# MCU.net
KiCad netlist of a schematic drawn in Altium Designer
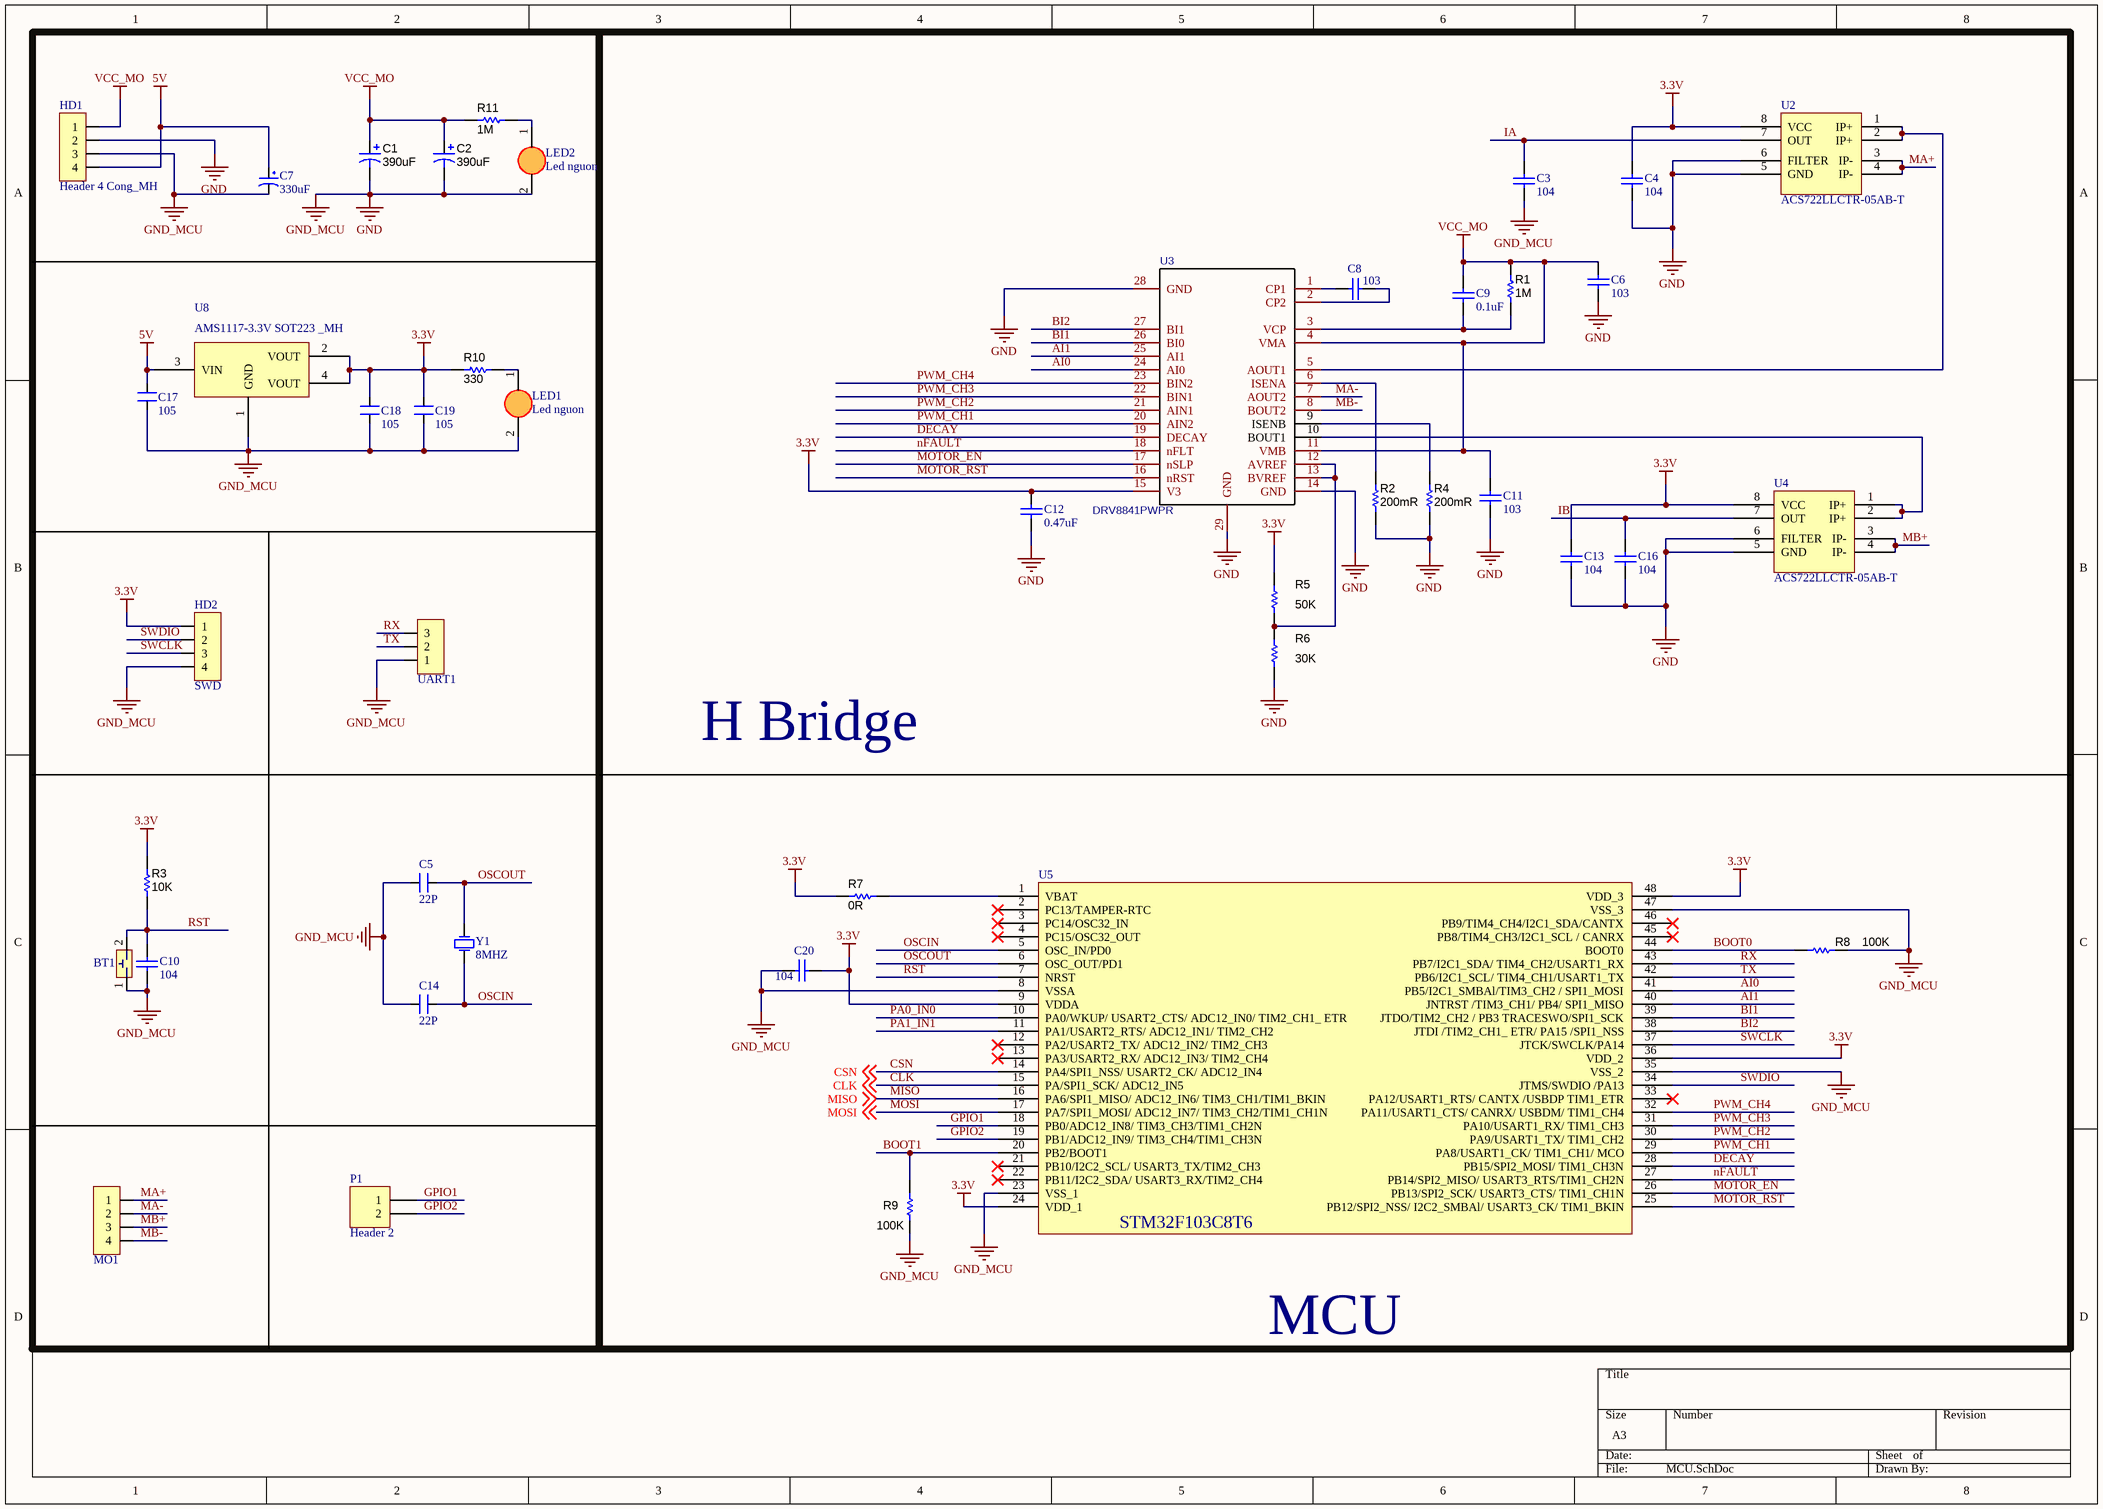
[diagram p0: MCU.SchDoc]

(export (version "E")
  (design (tool "Eeschema 10.0.6"))
  (components
    (comp (ref "BT1")
      (value "BUTTON 4P SMD_MH")
      (footprint "BUTTON 2P SMD")
      (description "Nút nhấn 4 chân, dán")
      (libsource (lib "MH_DA_THU_VIEN_16122016") (part "BUTTON 4P SMD_MH"))
    )
    (comp (ref "C1")
      (value "390uF")
      (footprint "CP1/3.0")
      (fields
        (field (name "PARTNUMBER") "UHW1H391MPD6")
        (field (name "MANUFACTURER") "Nichicon")
        (field (name "VALUEDISPLAYED") "390uF")
        (field (name "PUBLISHER") "Texas Instruments")
      )
      (libsource (lib "mySch") (part "Capacitor TuHoa"))
    )
    (comp (ref "C2")
      (value "390uF")
      (footprint "CP1/3.0")
      (fields
        (field (name "PARTNUMBER") "UHW1H391MPD6")
        (field (name "MANUFACTURER") "Nichicon")
        (field (name "VALUEDISPLAYED") "390uF")
        (field (name "PUBLISHER") "Texas Instruments")
      )
      (libsource (lib "mySch") (part "Capacitor TuHoa"))
    )
    (comp (ref "C3")
      (value "104")
      (footprint "0805_HV")
      (description "Ceramic Chip Capacitor - Standard")
      (fields (field (name "PUBLISHER") "Altium Limited"))
      (libsource (lib "mySch") (part "Capacitor 0805"))
    )
    (comp (ref "C4")
      (value "104")
      (footprint "0805_HV")
      (description "Ceramic Chip Capacitor - Standard")
      (fields (field (name "PUBLISHER") "Altium Limited"))
      (libsource (lib "mySch") (part "Capacitor 0805"))
    )
    (comp (ref "C5")
      (value "22P")
      (footprint "0805_HV")
      (description "Cap SMD")
      (libsource (lib "hatcatbietbay") (part "CM"))
    )
    (comp (ref "C6")
      (value "103")
      (footprint "0805_HV")
      (description "Ceramic Chip Capacitor - Standard")
      (fields (field (name "PUBLISHER") "Altium Limited"))
      (libsource (lib "mySch") (part "Capacitor 0805"))
    )
    (comp (ref "C7")
      (value "330uF")
      (footprint "TU_NHOM_220uF_25V_MH")
      (description "TU_NHOM_330uF_16V_MH")
      (libsource (lib "MH_DA_THU_VIEN_16122016") (part "TU_NHOM_330uF_16V_MH"))
    )
    (comp (ref "C8")
      (value "103")
      (footprint "0805_HV")
      (description "Ceramic Chip Capacitor - Standard")
      (fields (field (name "PUBLISHER") "Altium Limited"))
      (libsource (lib "mySch") (part "Capacitor 0805"))
    )
    (comp (ref "C9")
      (value "0.1uF")
      (footprint "0805_HV")
      (description "Ceramic Chip Capacitor - Standard")
      (fields (field (name "PUBLISHER") "Altium Limited"))
      (libsource (lib "mySch") (part "Capacitor 0805"))
    )
    (comp (ref "C10")
      (value "104")
      (footprint "0805_HV")
      (description "Ceramic Chip Capacitor - Standard")
      (fields (field (name "PUBLISHER") "Altium Limited"))
      (libsource (lib "mySch") (part "Capacitor 0805"))
    )
    (comp (ref "C11")
      (value "103")
      (footprint "0805_HV")
      (description "Ceramic Chip Capacitor - Standard")
      (fields (field (name "PUBLISHER") "Altium Limited"))
      (libsource (lib "mySch") (part "Capacitor 0805"))
    )
    (comp (ref "C12")
      (value "0.47uF")
      (footprint "0805_HV")
      (description "Ceramic Chip Capacitor - Standard")
      (fields (field (name "PUBLISHER") "Altium Limited"))
      (libsource (lib "mySch") (part "Capacitor 0805"))
    )
    (comp (ref "C13")
      (value "104")
      (footprint "0805_HV")
      (description "Ceramic Chip Capacitor - Standard")
      (fields (field (name "PUBLISHER") "Altium Limited"))
      (libsource (lib "mySch") (part "Capacitor 0805"))
    )
    (comp (ref "C14")
      (value "22P")
      (footprint "0805_HV")
      (description "Cap SMD")
      (libsource (lib "hatcatbietbay") (part "CM"))
    )
    (comp (ref "C16")
      (value "104")
      (footprint "0805_HV")
      (description "Ceramic Chip Capacitor - Standard")
      (fields (field (name "PUBLISHER") "Altium Limited"))
      (libsource (lib "mySch") (part "Capacitor 0805"))
    )
    (comp (ref "C17")
      (value "105")
      (footprint "0805_HV")
      (description "Cap SMD")
      (libsource (lib "hatcatbietbay") (part "CM"))
    )
    (comp (ref "C18")
      (value "105")
      (footprint "0805_HV")
      (description "Cap SMD")
      (libsource (lib "hatcatbietbay") (part "CM"))
    )
    (comp (ref "C19")
      (value "105")
      (footprint "0805_HV")
      (description "Cap SMD")
      (libsource (lib "hatcatbietbay") (part "CM"))
    )
    (comp (ref "C20")
      (value "104")
      (footprint "0805_HV")
      (description "Ceramic Chip Capacitor - Standard")
      (fields (field (name "PUBLISHER") "Altium Limited"))
      (libsource (lib "mySch") (part "Capacitor 0805"))
    )
    (comp (ref "HD1")
      (value "Header 4 Cong_MH")
      (footprint "HEADER 4")
      (description "Header 4P XH2.54 cong")
      (libsource (lib "MH_DA_THU_VIEN_16122016") (part "Header 4 Cong_MH"))
    )
    (comp (ref "HD2")
      (value "SWD")
      (footprint "HDR1X4")
      (description "Header 4P XH2.54 thẳng")
      (libsource (lib "") (part "Header 4_MH_1"))
    )
    (comp (ref "LED1")
      (value "Led nguon")
      (footprint "LED_0805")
      (description "LED 3mm")
      (libsource (lib "MH_DA_THU_VIEN_16122016") (part "LED SMD_0805_MH"))
    )
    (comp (ref "LED2")
      (value "Led nguon")
      (footprint "LED_0805")
      (description "LED 3mm")
      (libsource (lib "MH_DA_THU_VIEN_16122016") (part "LED SMD_0805_MH"))
    )
    (comp (ref "MO1")
      (value "Header 4_MH")
      (footprint "HEADER 4")
      (description "Header 4P XH2.54 thẳng")
      (libsource (lib "MH_DA_THU_VIEN_16122016") (part "Header 4_MH"))
    )
    (comp (ref "P1")
      (value "Header 2")
      (footprint "HDR1X2")
      (description "Header, 2-Pin")
      (fields (field (name "PUBLISHER") "Altium Limited"))
      (libsource (lib "Miscellaneous Connectors") (part "Header 2"))
    )
    (comp (ref "R1")
      (value "1M")
      (footprint "0805_HV")
      (description "RES, 100, 1%, 0.1 W, 0402")
      (fields
        (field (name "PARTNUMBER") "ERJ-2RKF1000X")
        (field (name "MANUFACTURER") "Panasonic")
        (field (name "PUBLISHER") "Texas Instruments")
      )
      (libsource (lib "mySch") (part "R nho"))
    )
    (comp (ref "R2")
      (value "RT0603DRE07140KL")
      (footprint "1210")
      (description "RES, 140 k, 0.5%, 0.1 W, 0603")
      (fields
        (field (name "VALUEDISPLAYED") "200mR")
        (field (name "MANUFACTURER") "Yageo America")
        (field (name "PUBLISHER") "Texas Instruments")
      )
      (libsource (lib "Resistor_0603") (part "RT0603DRE07140KL"))
    )
    (comp (ref "R3")
      (value "10K")
      (footprint "0805_HV")
      (description "RES, 100, 1%, 0.1 W, 0402")
      (fields
        (field (name "PARTNUMBER") "ERJ-2RKF1000X")
        (field (name "MANUFACTURER") "Panasonic")
        (field (name "PUBLISHER") "Texas Instruments")
      )
      (libsource (lib "mySch") (part "R nho"))
    )
    (comp (ref "R4")
      (value "RT0603DRE07140KL")
      (footprint "1210")
      (description "RES, 140 k, 0.5%, 0.1 W, 0603")
      (fields
        (field (name "VALUEDISPLAYED") "200mR")
        (field (name "MANUFACTURER") "Yageo America")
        (field (name "PUBLISHER") "Texas Instruments")
      )
      (libsource (lib "Resistor_0603") (part "RT0603DRE07140KL"))
    )
    (comp (ref "R5")
      (value "50K")
      (footprint "0805_HV")
      (description "RES, 100, 1%, 0.1 W, 0402")
      (fields
        (field (name "PARTNUMBER") "ERJ-2RKF1000X")
        (field (name "MANUFACTURER") "Panasonic")
        (field (name "PUBLISHER") "Texas Instruments")
      )
      (libsource (lib "mySch") (part "R nho"))
    )
    (comp (ref "R6")
      (value "30K")
      (footprint "0805_HV")
      (description "RES, 100, 1%, 0.1 W, 0402")
      (fields
        (field (name "PARTNUMBER") "ERJ-2RKF1000X")
        (field (name "MANUFACTURER") "Panasonic")
        (field (name "PUBLISHER") "Texas Instruments")
      )
      (libsource (lib "mySch") (part "R nho"))
    )
    (comp (ref "R7")
      (value "0R")
      (footprint "0805_HV")
      (description "RES, 100, 1%, 0.1 W, 0402")
      (fields
        (field (name "PARTNUMBER") "ERJ-2RKF1000X")
        (field (name "MANUFACTURER") "Panasonic")
        (field (name "PUBLISHER") "Texas Instruments")
      )
      (libsource (lib "mySch") (part "R nho"))
    )
    (comp (ref "R8")
      (value "100K")
      (footprint "0805_HV")
      (description "RES, 100, 1%, 0.1 W, 0402")
      (fields
        (field (name "PARTNUMBER") "ERJ-2RKF1000X")
        (field (name "MANUFACTURER") "Panasonic")
        (field (name "PUBLISHER") "Texas Instruments")
      )
      (libsource (lib "mySch") (part "R nho"))
    )
    (comp (ref "R9")
      (value "100K")
      (footprint "0805_HV")
      (description "RES, 100, 1%, 0.1 W, 0402")
      (fields
        (field (name "PARTNUMBER") "ERJ-2RKF1000X")
        (field (name "MANUFACTURER") "Panasonic")
        (field (name "PUBLISHER") "Texas Instruments")
      )
      (libsource (lib "mySch") (part "R nho"))
    )
    (comp (ref "R10")
      (value "330")
      (footprint "0805_HV")
      (description "RES, 100, 1%, 0.1 W, 0402")
      (fields
        (field (name "PARTNUMBER") "ERJ-2RKF1000X")
        (field (name "MANUFACTURER") "Panasonic")
        (field (name "PUBLISHER") "Texas Instruments")
      )
      (libsource (lib "mySch") (part "R nho"))
    )
    (comp (ref "R11")
      (value "1M")
      (footprint "0805_HV")
      (description "RES, 100, 1%, 0.1 W, 0402")
      (fields
        (field (name "PARTNUMBER") "ERJ-2RKF1000X")
        (field (name "MANUFACTURER") "Panasonic")
        (field (name "PUBLISHER") "Texas Instruments")
      )
      (libsource (lib "mySch") (part "R nho"))
    )
    (comp (ref "U2")
      (value "ACS722LLCTR-05AB-T")
      (footprint "SOP 8")
      (libsource (lib "mySch") (part "ACS712"))
    )
    (comp (ref "U3")
      (value "DRV8841PWPR")
      (footprint "TSSOP-28EP")
      (fields (field (name "BOM_SUPPLIER PART") "C36542"))
      (libsource (lib "Schlib1") (part "DRV8841PWPR"))
    )
    (comp (ref "U4")
      (value "ACS722LLCTR-05AB-T")
      (footprint "SOP 8")
      (libsource (lib "mySch") (part "ACS712"))
    )
    (comp (ref "U5")
      (value "STM32F103C8T6 LQFP48 _MH")
      (footprint "LQFP48")
      (libsource (lib "MH_DA_THU_VIEN_16122016") (part "STM32F103C8T6 LQFP48 _MH"))
    )
    (comp (ref "U8")
      (value "AMS1117-3.3V SOT223 _MH")
      (footprint "SOT223")
      (libsource (lib "MH_DA_THU_VIEN_16122016") (part "AMS1117-3.3V SOT223 _MH"))
    )
    (comp (ref "UART1")
      (value "Header 3_MH")
      (footprint "HDR1X3")
      (description "Header 3P XH2.54 thẳng")
      (libsource (lib "MH_DA_THU_VIEN_16122016") (part "Header 3_MH"))
    )
    (comp (ref "Y1")
      (value "8MHZ")
      (footprint "XTAL 49S SMD")
      (description "Crystal Oscillator")
      (fields (field (name "PUBLISHER") "Altium Limited"))
      (libsource (lib "MH_DA_THU_VIEN_16122016") (part "CRYSTAL_49S DIP_MH"))
    )
  )
  (nets
    (net (code "1") (name "/AI0") (class "Default")
      (node (ref "U3") (pin "24") (pinfunction "AI0_24") (pintype "passive"))
      (node (ref "U5") (pin "41") (pinfunction "PB5/I2C1_SMBAl/TIM3_CH2_/_SPI1_MOSI_41") (pintype "passive"))
    )
    (net (code "2") (name "/AI1") (class "Default")
      (node (ref "U3") (pin "25") (pinfunction "AI1_25") (pintype "passive"))
      (node (ref "U5") (pin "40") (pinfunction "JNTRST_/TIM3_CH1/_PB4/_SPI1_MISO_40") (pintype "passive"))
    )
    (net (code "3") (name "/BI1") (class "Default")
      (node (ref "U3") (pin "26") (pinfunction "BI0_26") (pintype "passive"))
      (node (ref "U5") (pin "39") (pinfunction "JTDO/TIM2_CH2_/_PB3_TRACESWO/SPI1_SCK_39") (pintype "passive"))
    )
    (net (code "4") (name "/BI2") (class "Default")
      (node (ref "U3") (pin "27") (pinfunction "BI1_27") (pintype "passive"))
      (node (ref "U5") (pin "38") (pinfunction "JTDI_/TIM2_CH1__ETR/_PA15_/SPI1_NSS_38") (pintype "passive"))
    )
    (net (code "5") (name "/BOOT0") (class "Default")
      (node (ref "R8") (pin "2") (pinfunction "2_2") (pintype "passive"))
      (node (ref "U5") (pin "44") (pinfunction "BOOT0_44") (pintype "passive"))
    )
    (net (code "6") (name "/BOOT1") (class "Default")
      (node (ref "R9") (pin "1") (pinfunction "1_1") (pintype "passive"))
      (node (ref "U5") (pin "20") (pinfunction "PB2/BOOT1_20") (pintype "passive"))
    )
    (net (code "7") (name "/DECAY") (class "Default")
      (node (ref "U3") (pin "19") (pinfunction "DECAY_19") (pintype "passive"))
      (node (ref "U5") (pin "28") (pinfunction "PB15/SPI2_MOSI/_TIM1_CH3N_28") (pintype "passive"))
    )
    (net (code "8") (name "/GPIO1") (class "Default")
      (node (ref "P1") (pin "1") (pinfunction "1_1") (pintype "passive"))
      (node (ref "U5") (pin "18") (pinfunction "PB0/ADC12_IN8/_TIM3_CH3/TIM1_CH2N_18") (pintype "passive"))
    )
    (net (code "9") (name "/GPIO2") (class "Default")
      (node (ref "P1") (pin "2") (pinfunction "2_2") (pintype "passive"))
      (node (ref "U5") (pin "19") (pinfunction "PB1/ADC12_IN9/_TIM3_CH4/TIM1_CH3N_19") (pintype "passive"))
    )
    (net (code "10") (name "/IA") (class "Default")
      (node (ref "C3") (pin "2") (pinfunction "2_2") (pintype "passive"))
      (node (ref "U2") (pin "7") (pinfunction "OUT_7") (pintype "passive"))
    )
    (net (code "11") (name "/IB") (class "Default")
      (node (ref "C16") (pin "2") (pinfunction "2_2") (pintype "passive"))
      (node (ref "U4") (pin "7") (pinfunction "OUT_7") (pintype "passive"))
    )
    (net (code "12") (name "/MA+") (class "Default")
      (node (ref "MO1") (pin "1") (pinfunction "1_1") (pintype "passive"))
      (node (ref "U2") (pin "3") (pinfunction "IP-_3") (pintype "passive"))
      (node (ref "U2") (pin "4") (pinfunction "IP-_4") (pintype "passive"))
    )
    (net (code "13") (name "/MA-") (class "Default")
      (node (ref "MO1") (pin "2") (pinfunction "2_2") (pintype "passive"))
      (node (ref "U3") (pin "7") (pinfunction "AOUT2_7") (pintype "passive"))
    )
    (net (code "14") (name "/MB+") (class "Default")
      (node (ref "MO1") (pin "3") (pinfunction "3_3") (pintype "passive"))
      (node (ref "U4") (pin "3") (pinfunction "IP-_3") (pintype "passive"))
      (node (ref "U4") (pin "4") (pinfunction "IP-_4") (pintype "passive"))
    )
    (net (code "15") (name "/MB-") (class "Default")
      (node (ref "MO1") (pin "4") (pinfunction "4_4") (pintype "passive"))
      (node (ref "U3") (pin "8") (pinfunction "BOUT2_8") (pintype "passive"))
    )
    (net (code "16") (name "/MOTOR_EN") (class "Default")
      (node (ref "U3") (pin "17") (pinfunction "nSLP_17") (pintype "passive"))
      (node (ref "U5") (pin "26") (pinfunction "PB13/SPI2_SCK/_USART3_CTS/_TIM1_CH1N_26") (pintype "passive"))
    )
    (net (code "17") (name "/MOTOR_RST") (class "Default")
      (node (ref "U3") (pin "16") (pinfunction "nRST_16") (pintype "passive"))
      (node (ref "U5") (pin "25") (pinfunction "PB12/SPI2_NSS/_I2C2_SMBAl/_USART3_CK/_TIM1_BKIN_25") (pintype "passive"))
    )
    (net (code "18") (name "/OSCIN") (class "Default")
      (node (ref "C14") (pin "2") (pinfunction "2_2") (pintype "passive"))
      (node (ref "U5") (pin "5") (pinfunction "OSC_IN/PD0_5") (pintype "passive"))
      (node (ref "Y1") (pin "2") (pinfunction "OSC2_2") (pintype "passive"))
    )
    (net (code "19") (name "/OSCOUT") (class "Default")
      (node (ref "C5") (pin "2") (pinfunction "2_2") (pintype "passive"))
      (node (ref "U5") (pin "6") (pinfunction "OSC_OUT/PD1_6") (pintype "passive"))
      (node (ref "Y1") (pin "1") (pinfunction "OSC1_1") (pintype "passive"))
    )
    (net (code "20") (name "/PA0_IN0") (class "Default")
      (node (ref "U5") (pin "10") (pinfunction "PA0/WKUP/_USART2_CTS/_ADC12_IN0/_TIM2_CH1__ETR_10") (pintype "passive"))
    )
    (net (code "21") (name "/PA1_IN1") (class "Default")
      (node (ref "U5") (pin "11") (pinfunction "PA1/USART2_RTS/_ADC12_IN1/_TIM2_CH2_11") (pintype "passive"))
    )
    (net (code "22") (name "/PWM_CH1") (class "Default")
      (node (ref "U3") (pin "20") (pinfunction "AIN2_20") (pintype "passive"))
      (node (ref "U5") (pin "29") (pinfunction "PA8/USART1_CK/_TIM1_CH1/_MCO_29") (pintype "passive"))
    )
    (net (code "23") (name "/PWM_CH2") (class "Default")
      (node (ref "U3") (pin "21") (pinfunction "AIN1_21") (pintype "passive"))
      (node (ref "U5") (pin "30") (pinfunction "PA9/USART1_TX/_TIM1_CH2_30") (pintype "passive"))
    )
    (net (code "24") (name "/PWM_CH3") (class "Default")
      (node (ref "U3") (pin "22") (pinfunction "BIN1_22") (pintype "passive"))
      (node (ref "U5") (pin "31") (pinfunction "PA10/USART1_RX/_TIM1_CH3_31") (pintype "passive"))
    )
    (net (code "25") (name "/PWM_CH4") (class "Default")
      (node (ref "U3") (pin "23") (pinfunction "BIN2_23") (pintype "passive"))
      (node (ref "U5") (pin "32") (pinfunction "PA11/USART1_CTS/_CANRX/_USBDM/_TIM1_CH4_32") (pintype "passive"))
    )
    (net (code "26") (name "/RST") (class "Default")
      (node (ref "BT1") (pin "2") (pinfunction "2_2") (pintype "passive"))
      (node (ref "C10") (pin "2") (pinfunction "2_2") (pintype "passive"))
      (node (ref "R3") (pin "1") (pinfunction "1_1") (pintype "passive"))
      (node (ref "U5") (pin "7") (pinfunction "NRST_7") (pintype "passive"))
    )
    (net (code "27") (name "/RX") (class "Default")
      (node (ref "U5") (pin "43") (pinfunction "PB7/I2C1_SDA/_TIM4_CH2/USART1_RX_43") (pintype "passive"))
      (node (ref "UART1") (pin "3") (pinfunction "3_3") (pintype "passive"))
    )
    (net (code "28") (name "/SWCLK") (class "Default")
      (node (ref "HD2") (pin "3") (pinfunction "3_3") (pintype "passive"))
      (node (ref "U5") (pin "37") (pinfunction "JTCK/SWCLK/PA14_37") (pintype "passive"))
    )
    (net (code "29") (name "/SWDIO") (class "Default")
      (node (ref "HD2") (pin "2") (pinfunction "2_2") (pintype "passive"))
      (node (ref "U5") (pin "34") (pinfunction "JTMS/SWDIO_/PA13_34") (pintype "passive"))
    )
    (net (code "30") (name "/TX") (class "Default")
      (node (ref "U5") (pin "42") (pinfunction "PB6/I2C1_SCL/_TIM4_CH1/USART1_TX_42") (pintype "passive"))
      (node (ref "UART1") (pin "2") (pinfunction "2_2") (pintype "passive"))
    )
    (net (code "31") (name "/nFAULT") (class "Default")
      (node (ref "U3") (pin "18") (pinfunction "nFLT_18") (pintype "passive"))
      (node (ref "U5") (pin "27") (pinfunction "PB14/SPI2_MISO/_USART3_RTS/TIM1_CH2N_27") (pintype "passive"))
    )
    (net (code "32") (name "3.3V") (class "Default")
      (node (ref "C12") (pin "2") (pinfunction "2_2") (pintype "passive"))
      (node (ref "C13") (pin "2") (pinfunction "2_2") (pintype "passive"))
      (node (ref "C18") (pin "2") (pinfunction "2_2") (pintype "passive"))
      (node (ref "C19") (pin "2") (pinfunction "2_2") (pintype "passive"))
      (node (ref "C20") (pin "2") (pinfunction "2_2") (pintype "passive"))
      (node (ref "C4") (pin "2") (pinfunction "2_2") (pintype "passive"))
      (node (ref "HD2") (pin "1") (pinfunction "1_1") (pintype "passive"))
      (node (ref "R10") (pin "2") (pinfunction "2_2") (pintype "passive"))
      (node (ref "R3") (pin "2") (pinfunction "2_2") (pintype "passive"))
      (node (ref "R5") (pin "2") (pinfunction "2_2") (pintype "passive"))
      (node (ref "R7") (pin "2") (pinfunction "2_2") (pintype "passive"))
      (node (ref "U2") (pin "8") (pinfunction "VCC_8") (pintype "passive"))
      (node (ref "U3") (pin "15") (pinfunction "V3_15") (pintype "passive"))
      (node (ref "U4") (pin "8") (pinfunction "VCC_8") (pintype "passive"))
      (node (ref "U5") (pin "24") (pinfunction "VDD_1_24") (pintype "passive"))
      (node (ref "U5") (pin "36") (pinfunction "VDD_2_36") (pintype "passive"))
      (node (ref "U5") (pin "48") (pinfunction "VDD_3_48") (pintype "passive"))
      (node (ref "U5") (pin "9") (pinfunction "VDDA_9") (pintype "passive"))
      (node (ref "U8") (pin "2") (pinfunction "VOUT_2") (pintype "passive"))
      (node (ref "U8") (pin "4") (pinfunction "VOUT_4") (pintype "passive"))
    )
    (net (code "33") (name "5V") (class "Default")
      (node (ref "C17") (pin "2") (pinfunction "2_2") (pintype "passive"))
      (node (ref "C7") (pin "1") (pinfunction "1_1") (pintype "passive"))
      (node (ref "HD1") (pin "4") (pinfunction "4_4") (pintype "passive"))
      (node (ref "U8") (pin "3") (pinfunction "VIN_3") (pintype "passive"))
    )
    (net (code "34") (name "CLK") (class "Default")
      (node (ref "U5") (pin "15") (pinfunction "PA/SPI1_SCK/_ADC12_IN5_15") (pintype "passive"))
    )
    (net (code "35") (name "CSN") (class "Default")
      (node (ref "U5") (pin "14") (pinfunction "PA4/SPI1_NSS/_USART2_CK/_ADC12_IN4_14") (pintype "passive"))
    )
    (net (code "36") (name "GND") (class "Default")
      (node (ref "BT1") (pin "1") (pinfunction "1_1") (pintype "passive"))
      (node (ref "C1") (pin "2") (pinfunction "-_2") (pintype "passive"))
      (node (ref "C10") (pin "1") (pinfunction "1_1") (pintype "passive"))
      (node (ref "C11") (pin "1") (pinfunction "1_1") (pintype "passive"))
      (node (ref "C12") (pin "1") (pinfunction "1_1") (pintype "passive"))
      (node (ref "C13") (pin "1") (pinfunction "1_1") (pintype "passive"))
      (node (ref "C14") (pin "1") (pinfunction "1_1") (pintype "passive"))
      (node (ref "C16") (pin "1") (pinfunction "1_1") (pintype "passive"))
      (node (ref "C17") (pin "1") (pinfunction "1_1") (pintype "passive"))
      (node (ref "C18") (pin "1") (pinfunction "1_1") (pintype "passive"))
      (node (ref "C19") (pin "1") (pinfunction "1_1") (pintype "passive"))
      (node (ref "C2") (pin "2") (pinfunction "-_2") (pintype "passive"))
      (node (ref "C20") (pin "1") (pinfunction "1_1") (pintype "passive"))
      (node (ref "C3") (pin "1") (pinfunction "1_1") (pintype "passive"))
      (node (ref "C4") (pin "1") (pinfunction "1_1") (pintype "passive"))
      (node (ref "C5") (pin "1") (pinfunction "1_1") (pintype "passive"))
      (node (ref "C6") (pin "1") (pinfunction "1_1") (pintype "passive"))
      (node (ref "C7") (pin "2") (pinfunction "2_2") (pintype "passive"))
      (node (ref "HD1") (pin "2") (pinfunction "2_2") (pintype "passive"))
      (node (ref "HD1") (pin "3") (pinfunction "3_3") (pintype "passive"))
      (node (ref "HD2") (pin "4") (pinfunction "4_4") (pintype "passive"))
      (node (ref "LED1") (pin "2") (pinfunction "K_2") (pintype "passive"))
      (node (ref "LED2") (pin "2") (pinfunction "K_2") (pintype "passive"))
      (node (ref "R2") (pin "1") (pinfunction "1_1") (pintype "passive"))
      (node (ref "R4") (pin "1") (pinfunction "1_1") (pintype "passive"))
      (node (ref "R6") (pin "1") (pinfunction "1_1") (pintype "passive"))
      (node (ref "R8") (pin "1") (pinfunction "1_1") (pintype "passive"))
      (node (ref "R9") (pin "2") (pinfunction "2_2") (pintype "passive"))
      (node (ref "U2") (pin "5") (pinfunction "GND_5") (pintype "passive"))
      (node (ref "U2") (pin "6") (pinfunction "FILTER_6") (pintype "passive"))
      (node (ref "U3") (pin "14") (pinfunction "GND_14") (pintype "passive"))
      (node (ref "U3") (pin "28") (pinfunction "GND_28") (pintype "passive"))
      (node (ref "U3") (pin "29") (pinfunction "GND_29") (pintype "passive"))
      (node (ref "U4") (pin "5") (pinfunction "GND_5") (pintype "passive"))
      (node (ref "U4") (pin "6") (pinfunction "FILTER_6") (pintype "passive"))
      (node (ref "U5") (pin "23") (pinfunction "VSS_1_23") (pintype "passive"))
      (node (ref "U5") (pin "35") (pinfunction "VSS_2_35") (pintype "passive"))
      (node (ref "U5") (pin "47") (pinfunction "VSS_3_47") (pintype "passive"))
      (node (ref "U5") (pin "8") (pinfunction "VSSA_8") (pintype "passive"))
      (node (ref "U8") (pin "1") (pinfunction "GND_1") (pintype "passive"))
      (node (ref "UART1") (pin "1") (pinfunction "1_1") (pintype "passive"))
    )
    (net (code "37") (name "MISO") (class "Default")
      (node (ref "U5") (pin "16") (pinfunction "PA6/SPI1_MISO/_ADC12_IN6/_TIM3_CH1/TIM1_BKIN_16") (pintype "passive"))
    )
    (net (code "38") (name "MOSI") (class "Default")
      (node (ref "U5") (pin "17") (pinfunction "PA7/SPI1_MOSI/_ADC12_IN7/_TIM3_CH2/TIM1_CH1N_17") (pintype "passive"))
    )
    (net (code "39") (name "Net-(LED1-A)") (class "Default")
      (node (ref "LED1") (pin "1") (pinfunction "A_1") (pintype "passive"))
      (node (ref "R10") (pin "1") (pinfunction "1_1") (pintype "passive"))
    )
    (net (code "40") (name "Net-(LED2-A)") (class "Default")
      (node (ref "LED2") (pin "1") (pinfunction "A_1") (pintype "passive"))
      (node (ref "R11") (pin "1") (pinfunction "1_1") (pintype "passive"))
    )
    (net (code "41") (name "Net-(U3-AOUT1)") (class "Default")
      (node (ref "U2") (pin "1") (pinfunction "IP+_1") (pintype "passive"))
      (node (ref "U2") (pin "2") (pinfunction "IP+_2") (pintype "passive"))
      (node (ref "U3") (pin "5") (pinfunction "AOUT1_5") (pintype "passive"))
    )
    (net (code "42") (name "Net-(U3-AVREF)") (class "Default")
      (node (ref "R5") (pin "1") (pinfunction "1_1") (pintype "passive"))
      (node (ref "R6") (pin "2") (pinfunction "2_2") (pintype "passive"))
      (node (ref "U3") (pin "12") (pinfunction "AVREF_12") (pintype "passive"))
      (node (ref "U3") (pin "13") (pinfunction "BVREF_13") (pintype "passive"))
    )
    (net (code "43") (name "Net-(U3-BOUT1)") (class "Default")
      (node (ref "U3") (pin "10") (pinfunction "BOUT1_10") (pintype "passive"))
      (node (ref "U4") (pin "1") (pinfunction "IP+_1") (pintype "passive"))
      (node (ref "U4") (pin "2") (pinfunction "IP+_2") (pintype "passive"))
    )
    (net (code "44") (name "Net-(U3-CP1)") (class "Default")
      (node (ref "C8") (pin "2") (pinfunction "2_2") (pintype "passive"))
      (node (ref "U3") (pin "1") (pinfunction "CP1_1") (pintype "passive"))
    )
    (net (code "45") (name "Net-(U3-CP2)") (class "Default")
      (node (ref "C8") (pin "1") (pinfunction "1_1") (pintype "passive"))
      (node (ref "U3") (pin "2") (pinfunction "CP2_2") (pintype "passive"))
    )
    (net (code "46") (name "Net-(U3-ISENA)") (class "Default")
      (node (ref "R2") (pin "2") (pinfunction "2_2") (pintype "passive"))
      (node (ref "U3") (pin "6") (pinfunction "ISENA_6") (pintype "passive"))
    )
    (net (code "47") (name "Net-(U3-ISENB)") (class "Default")
      (node (ref "R4") (pin "2") (pinfunction "2_2") (pintype "passive"))
      (node (ref "U3") (pin "9") (pinfunction "ISENB_9") (pintype "passive"))
    )
    (net (code "48") (name "Net-(U3-VCP)") (class "Default")
      (node (ref "C9") (pin "1") (pinfunction "1_1") (pintype "passive"))
      (node (ref "R1") (pin "1") (pinfunction "1_1") (pintype "passive"))
      (node (ref "U3") (pin "3") (pinfunction "VCP_3") (pintype "passive"))
    )
    (net (code "49") (name "Net-(U5-VBAT)") (class "Default")
      (node (ref "R7") (pin "1") (pinfunction "1_1") (pintype "passive"))
      (node (ref "U5") (pin "1") (pinfunction "VBAT_1") (pintype "passive"))
    )
    (net (code "50") (name "VCC_MO") (class "Default")
      (node (ref "C1") (pin "1") (pinfunction "+_1") (pintype "passive"))
      (node (ref "C11") (pin "2") (pinfunction "2_2") (pintype "passive"))
      (node (ref "C2") (pin "1") (pinfunction "+_1") (pintype "passive"))
      (node (ref "C6") (pin "2") (pinfunction "2_2") (pintype "passive"))
      (node (ref "C9") (pin "2") (pinfunction "2_2") (pintype "passive"))
      (node (ref "HD1") (pin "1") (pinfunction "1_1") (pintype "passive"))
      (node (ref "R1") (pin "2") (pinfunction "2_2") (pintype "passive"))
      (node (ref "R11") (pin "2") (pinfunction "2_2") (pintype "passive"))
      (node (ref "U3") (pin "11") (pinfunction "VMB_11") (pintype "passive"))
      (node (ref "U3") (pin "4") (pinfunction "VMA_4") (pintype "passive"))
    )
    (net (code "51") (name "unconnected-(U5-PA2{slash}USART2_TX{slash}_ADC12_IN2{slash}_TIM2_CH3-Pad12)") (class "Default")
      (node (ref "U5") (pin "12") (pinfunction "PA2/USART2_TX/_ADC12_IN2/_TIM2_CH3_12") (pintype "passive+no_connect"))
    )
    (net (code "52") (name "unconnected-(U5-PA3{slash}USART2_RX{slash}_ADC12_IN3{slash}_TIM2_CH4-Pad13)") (class "Default")
      (node (ref "U5") (pin "13") (pinfunction "PA3/USART2_RX/_ADC12_IN3/_TIM2_CH4_13") (pintype "passive+no_connect"))
    )
    (net (code "53") (name "unconnected-(U5-PA12{slash}USART1_RTS{slash}_CANTX_{slash}USBDP_TIM1_ETR-Pad33)") (class "Default")
      (node (ref "U5") (pin "33") (pinfunction "PA12/USART1_RTS/_CANTX_/USBDP_TIM1_ETR_33") (pintype "passive+no_connect"))
    )
    (net (code "54") (name "unconnected-(U5-PB8{slash}TIM4_CH3{slash}I2C1_SCL_{slash}_CANRX-Pad45)") (class "Default")
      (node (ref "U5") (pin "45") (pinfunction "PB8/TIM4_CH3/I2C1_SCL_/_CANRX_45") (pintype "passive+no_connect"))
    )
    (net (code "55") (name "unconnected-(U5-PB9{slash}TIM4_CH4{slash}I2C1_SDA{slash}CANTX-Pad46)") (class "Default")
      (node (ref "U5") (pin "46") (pinfunction "PB9/TIM4_CH4/I2C1_SDA/CANTX_46") (pintype "passive+no_connect"))
    )
    (net (code "56") (name "unconnected-(U5-PB10{slash}I2C2_SCL{slash}_USART3_TX{slash}TIM2_CH3-Pad21)") (class "Default")
      (node (ref "U5") (pin "21") (pinfunction "PB10/I2C2_SCL/_USART3_TX/TIM2_CH3_21") (pintype "passive+no_connect"))
    )
    (net (code "57") (name "unconnected-(U5-PB11{slash}I2C2_SDA{slash}_USART3_RX{slash}TIM2_CH4-Pad22)") (class "Default")
      (node (ref "U5") (pin "22") (pinfunction "PB11/I2C2_SDA/_USART3_RX/TIM2_CH4_22") (pintype "passive+no_connect"))
    )
    (net (code "58") (name "unconnected-(U5-PC13{slash}TAMPER-RTC-Pad2)") (class "Default")
      (node (ref "U5") (pin "2") (pinfunction "PC13/TAMPER-RTC_2") (pintype "passive+no_connect"))
    )
    (net (code "59") (name "unconnected-(U5-PC14{slash}OSC32_IN-Pad3)") (class "Default")
      (node (ref "U5") (pin "3") (pinfunction "PC14/OSC32_IN_3") (pintype "passive+no_connect"))
    )
    (net (code "60") (name "unconnected-(U5-PC15{slash}OSC32_OUT-Pad4)") (class "Default")
      (node (ref "U5") (pin "4") (pinfunction "PC15/OSC32_OUT_4") (pintype "passive+no_connect"))
    )
  )
)
